# 464421_22-01_RF_IN.net
KiCad netlist of a schematic drawn in Altium Designer
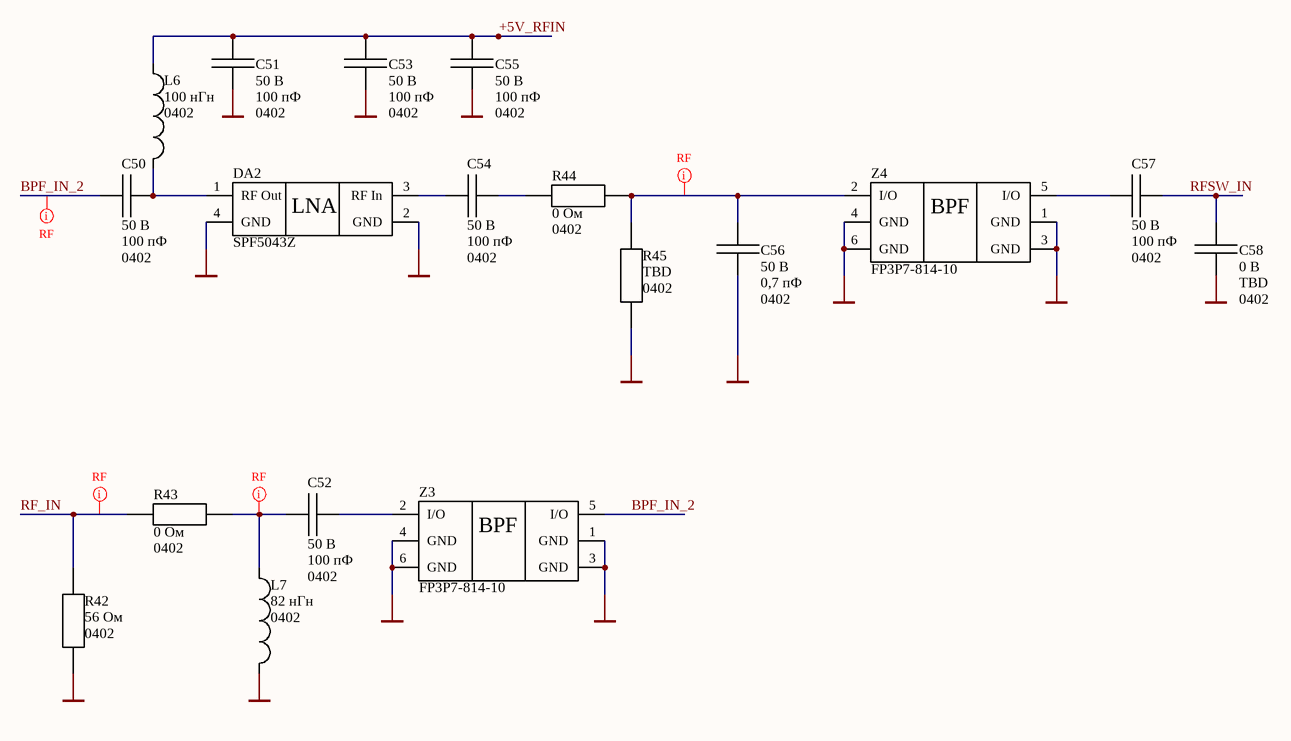
[diagram p0: МПСУ.464421.22-01 RF_IN.SchDoc]

(export (version "E")
  (design (tool "Eeschema 10.0.6"))
  (components
    (comp (ref "C50")
      (value "100 пФ")
      (footprint "Passive_V2_0:CAPC100X50X55L20N")
      (description "Capacitor 0402")
      (fields
        (field (name "PARTNUMBER") "GRM1555C1H101JZ01D")
        (field (name "MANUFACTURER") "Murata")
        (field (name "PEAK_CONDITION") "50 В")
        (field (name "PACKAGE") "0402")
        (field (name "DESIGNER") "Свидерский")
      )
      (libsource (lib "Passive_V2_0") (part "C 0402"))
    )
    (comp (ref "C51")
      (value "100 пФ")
      (footprint "Passive_V2_0:CAPC100X50X55L20N")
      (description "Capacitor 0402")
      (fields
        (field (name "PARTNUMBER") "GRM1555C1H101JZ01D")
        (field (name "MANUFACTURER") "Murata")
        (field (name "PEAK_CONDITION") "50 В")
        (field (name "PACKAGE") "0402")
        (field (name "DESIGNER") "Свидерский")
      )
      (libsource (lib "Passive_V2_0") (part "C 0402"))
    )
    (comp (ref "C52")
      (value "100 пФ")
      (footprint "Passive_V2_0:CAPC100X50X55L20N")
      (description "Capacitor 0402")
      (fields
        (field (name "PARTNUMBER") "GRM1555C1H101JZ01D")
        (field (name "MANUFACTURER") "Murata")
        (field (name "PEAK_CONDITION") "50 В")
        (field (name "PACKAGE") "0402")
        (field (name "DESIGNER") "Свидерский")
      )
      (libsource (lib "Passive_V2_0") (part "C 0402"))
    )
    (comp (ref "C53")
      (value "100 пФ")
      (footprint "Passive_V2_0:CAPC100X50X55L20N")
      (description "Capacitor 0402")
      (fields
        (field (name "PARTNUMBER") "GRM1555C1H101JZ01D")
        (field (name "MANUFACTURER") "Murata")
        (field (name "PEAK_CONDITION") "50 В")
        (field (name "PACKAGE") "0402")
        (field (name "DESIGNER") "Свидерский")
      )
      (libsource (lib "Passive_V2_0") (part "C 0402"))
    )
    (comp (ref "C54")
      (value "100 пФ")
      (footprint "Passive_V2_0:CAPC100X50X55L20N")
      (description "Capacitor 0402")
      (fields
        (field (name "PARTNUMBER") "GRM1555C1H101JZ01D")
        (field (name "MANUFACTURER") "Murata")
        (field (name "PEAK_CONDITION") "50 В")
        (field (name "PACKAGE") "0402")
        (field (name "DESIGNER") "Свидерский")
      )
      (libsource (lib "Passive_V2_0") (part "C 0402"))
    )
    (comp (ref "C55")
      (value "100 пФ")
      (footprint "Passive_V2_0:CAPC100X50X55L20N")
      (description "Capacitor 0402")
      (fields
        (field (name "PARTNUMBER") "GRM1555C1H101JZ01D")
        (field (name "MANUFACTURER") "Murata")
        (field (name "PEAK_CONDITION") "50 В")
        (field (name "PACKAGE") "0402")
        (field (name "DESIGNER") "Свидерский")
      )
      (libsource (lib "Passive_V2_0") (part "C 0402"))
    )
    (comp (ref "C56")
      (value "0,7 пФ")
      (footprint "Passive_V2_0:CAPC100X50X55L20N")
      (description "Capacitor 0402")
      (fields
        (field (name "PARTNUMBER") "GRM1555C1HR70WA01D")
        (field (name "MANUFACTURER") "Murata")
        (field (name "PEAK_CONDITION") "50 В")
        (field (name "PACKAGE") "0402")
        (field (name "DESIGNER") "Свидерский")
      )
      (libsource (lib "Passive_V2_0") (part "C 0402"))
    )
    (comp (ref "C57")
      (value "100 пФ")
      (footprint "Passive_V2_0:CAPC100X50X55L20N")
      (description "Capacitor 0402")
      (fields
        (field (name "PARTNUMBER") "GRM1555C1H101JZ01D")
        (field (name "MANUFACTURER") "Murata")
        (field (name "PEAK_CONDITION") "50 В")
        (field (name "PACKAGE") "0402")
        (field (name "DESIGNER") "Свидерский")
      )
      (libsource (lib "Passive_V2_0") (part "C 0402"))
    )
    (comp (ref "C58")
      (value "TBD")
      (footprint "Passive_V2_0:CAPC100X50X55L20N")
      (description "Capacitor 0402")
      (fields
        (field (name "TOLERANCE") "0 %")
        (field (name "PEAK_CONDITION") "0 В")
        (field (name "PACKAGE") "0402")
        (field (name "Comment") "TBD 0402")
        (field (name "DESIGNER") "Свидерский")
      )
      (libsource (lib "Passive_V2_0") (part "C 0402"))
    )
    (comp (ref "DA2")
      (value "SPF5043Z")
      (footprint "IC_V2_0:SOT130P210X100-4N")
      (description "50 MHz to 4000 MHz Low-Noise Amplifier")
      (fields
        (field (name "MANUFACTURER") "Qorvo")
        (field (name "PARTNUMBER") "SPF5043Z")
        (field (name "DESIGNER") "Лазба")
      )
      (libsource (lib "IC_V2_0") (part "SPF5043Z"))
    )
    (comp (ref "L6")
      (value "100 нГн")
      (footprint "Passive_V2_0:INDC100X50X60L10N")
      (description "Inductor 0402")
      (fields
        (field (name "PARTNUMBER") "LQG15HNR10J02D")
        (field (name "TOLERANCE") "5 %")
        (field (name "PACKAGE") "0402")
        (field (name "DESIGNER") "Свидерский")
      )
      (libsource (lib "Passive_V2_0") (part "L 0402"))
    )
    (comp (ref "L7")
      (value "82 нГн")
      (footprint "Passive_V2_0:INDC100X50X60L10N")
      (description "Inductor 0402")
      (fields
        (field (name "PARTNUMBER") "LQG15HN82NJ02D")
        (field (name "TOLERANCE") "5 %")
        (field (name "PACKAGE") "0402")
        (field (name "DESIGNER") "Свидерский")
      )
      (libsource (lib "Passive_V2_0") (part "L 0402"))
    )
    (comp (ref "R42")
      (value "56 Ом")
      (footprint "Passive_V2_0:RESC100X50X40L25N")
      (description "Resistor 0402")
      (fields
        (field (name "PARTNUMBER") "CR-02FL6-56R")
        (field (name "TOLERANCE") "1 %")
        (field (name "PACKAGE") "0402")
        (field (name "DESIGNER") "Свидерский")
      )
      (libsource (lib "Passive_V2_0") (part "R 0402"))
    )
    (comp (ref "R43")
      (value "0 Ом")
      (footprint "Passive_V2_0:RESC100X50X40L25N")
      (description "Resistor 0402")
      (fields
        (field (name "PARTNUMBER") "RI0402L000JT")
        (field (name "TOLERANCE") "5 %")
        (field (name "PACKAGE") "0402")
        (field (name "DESIGNER") "Свидерский")
      )
      (libsource (lib "") (part "R 0402_1"))
    )
    (comp (ref "R44")
      (value "0 Ом")
      (footprint "Passive_V2_0:RESC100X50X40L25N")
      (description "Resistor 0402")
      (fields
        (field (name "PARTNUMBER") "RI0402L000JT")
        (field (name "TOLERANCE") "5 %")
        (field (name "PACKAGE") "0402")
        (field (name "DESIGNER") "Свидерский")
      )
      (libsource (lib "") (part "R 0402_1"))
    )
    (comp (ref "R45")
      (value "TBD")
      (footprint "Passive_V2_0:RESC100X50X40L25N")
      (description "Resistor 0402")
      (fields
        (field (name "TOLERANCE") "0 %")
        (field (name "PACKAGE") "0402")
        (field (name "Comment") "TBD 0402")
        (field (name "DESIGNER") "Свидерский")
      )
      (libsource (lib "Passive_V2_0") (part "R 0402"))
    )
    (comp (ref "Z3")
      (value "FP3P7-814-10")
      (footprint "Passive_V2_0:LCCS110P300X300X146-6N")
      (description "BandPass Filter")
      (fields
        (field (name "MANUFACTURER") "БУТИС")
        (field (name "PARTNUMBER") "FP3P7-814-10")
        (field (name "DESIGNER") "Лазба")
      )
      (libsource (lib "Passive_V2_0") (part "FP3P7-***-**"))
    )
    (comp (ref "Z4")
      (value "FP3P7-814-10")
      (footprint "Passive_V2_0:LCCS110P300X300X146-6N")
      (description "BandPass Filter")
      (fields
        (field (name "MANUFACTURER") "БУТИС")
        (field (name "PARTNUMBER") "FP3P7-814-10")
        (field (name "DESIGNER") "Лазба")
      )
      (libsource (lib "Passive_V2_0") (part "FP3P7-***-**"))
    )
  )
  (nets
    (net (code "1") (name "/+5V_RFIN") (class "Default")
      (node (ref "C51") (pin "1") (pinfunction "1_1") (pintype "passive"))
      (node (ref "C53") (pin "1") (pinfunction "1_1") (pintype "passive"))
      (node (ref "C55") (pin "1") (pinfunction "1_1") (pintype "passive"))
      (node (ref "L6") (pin "1") (pinfunction "1_1") (pintype "passive"))
    )
    (net (code "2") (name "/BPF_IN_2") (class "Default")
      (node (ref "C50") (pin "1") (pinfunction "1_1") (pintype "passive"))
      (node (ref "Z3") (pin "5") (pinfunction "I/O_5") (pintype "passive"))
    )
    (net (code "3") (name "/RFSW_IN") (class "Default")
      (node (ref "C57") (pin "2") (pinfunction "2_2") (pintype "passive"))
      (node (ref "C58") (pin "1") (pinfunction "1_1") (pintype "passive"))
    )
    (net (code "4") (name "/RF_IN") (class "Default")
      (node (ref "R42") (pin "1") (pinfunction "1_1") (pintype "passive"))
      (node (ref "R43") (pin "2") (pinfunction "2_2") (pintype "passive"))
    )
    (net (code "5") (name "GND") (class "Default")
      (node (ref "C51") (pin "2") (pinfunction "2_2") (pintype "passive"))
      (node (ref "C53") (pin "2") (pinfunction "2_2") (pintype "passive"))
      (node (ref "C55") (pin "2") (pinfunction "2_2") (pintype "passive"))
      (node (ref "C56") (pin "1") (pinfunction "1_1") (pintype "passive"))
      (node (ref "C58") (pin "2") (pinfunction "2_2") (pintype "passive"))
      (node (ref "DA2") (pin "2") (pinfunction "GND_2") (pintype "passive"))
      (node (ref "DA2") (pin "4") (pinfunction "GND_4") (pintype "passive"))
      (node (ref "L7") (pin "2") (pinfunction "2_2") (pintype "passive"))
      (node (ref "R42") (pin "2") (pinfunction "2_2") (pintype "passive"))
      (node (ref "R45") (pin "2") (pinfunction "2_2") (pintype "passive"))
      (node (ref "Z3") (pin "1") (pinfunction "GND_1") (pintype "passive"))
      (node (ref "Z3") (pin "3") (pinfunction "GND_3") (pintype "passive"))
      (node (ref "Z3") (pin "4") (pinfunction "GND_4") (pintype "passive"))
      (node (ref "Z3") (pin "6") (pinfunction "GND_6") (pintype "passive"))
      (node (ref "Z4") (pin "1") (pinfunction "GND_1") (pintype "passive"))
      (node (ref "Z4") (pin "3") (pinfunction "GND_3") (pintype "passive"))
      (node (ref "Z4") (pin "4") (pinfunction "GND_4") (pintype "passive"))
      (node (ref "Z4") (pin "6") (pinfunction "GND_6") (pintype "passive"))
    )
    (net (code "6") (name "Net-(C52-Pad1)") (class "Default")
      (node (ref "C52") (pin "1") (pinfunction "1_1") (pintype "passive"))
      (node (ref "L7") (pin "1") (pinfunction "1_1") (pintype "passive"))
      (node (ref "R43") (pin "1") (pinfunction "1_1") (pintype "passive"))
    )
    (net (code "7") (name "Net-(C52-Pad2)") (class "Default")
      (node (ref "C52") (pin "2") (pinfunction "2_2") (pintype "passive"))
      (node (ref "Z3") (pin "2") (pinfunction "I/O_2") (pintype "passive"))
    )
    (net (code "8") (name "Net-(C54-Pad2)") (class "Default")
      (node (ref "C54") (pin "2") (pinfunction "2_2") (pintype "passive"))
      (node (ref "R44") (pin "2") (pinfunction "2_2") (pintype "passive"))
    )
    (net (code "9") (name "Net-(C56-Pad2)") (class "Default")
      (node (ref "C56") (pin "2") (pinfunction "2_2") (pintype "passive"))
      (node (ref "R44") (pin "1") (pinfunction "1_1") (pintype "passive"))
      (node (ref "R45") (pin "1") (pinfunction "1_1") (pintype "passive"))
      (node (ref "Z4") (pin "2") (pinfunction "I/O_2") (pintype "passive"))
    )
    (net (code "10") (name "Net-(C57-Pad1)") (class "Default")
      (node (ref "C57") (pin "1") (pinfunction "1_1") (pintype "passive"))
      (node (ref "Z4") (pin "5") (pinfunction "I/O_5") (pintype "passive"))
    )
    (net (code "11") (name "Net-(DA2-RF_In)") (class "Default")
      (node (ref "C54") (pin "1") (pinfunction "1_1") (pintype "passive"))
      (node (ref "DA2") (pin "3") (pinfunction "RF_In_3") (pintype "passive"))
    )
    (net (code "12") (name "Net-(DA2-RF_Out)") (class "Default")
      (node (ref "C50") (pin "2") (pinfunction "2_2") (pintype "passive"))
      (node (ref "DA2") (pin "1") (pinfunction "RF_Out_1") (pintype "passive"))
      (node (ref "L6") (pin "2") (pinfunction "2_2") (pintype "passive"))
    )
  )
)
